# 05_POWER_old.net
KiCad netlist of a schematic drawn in Altium Designer
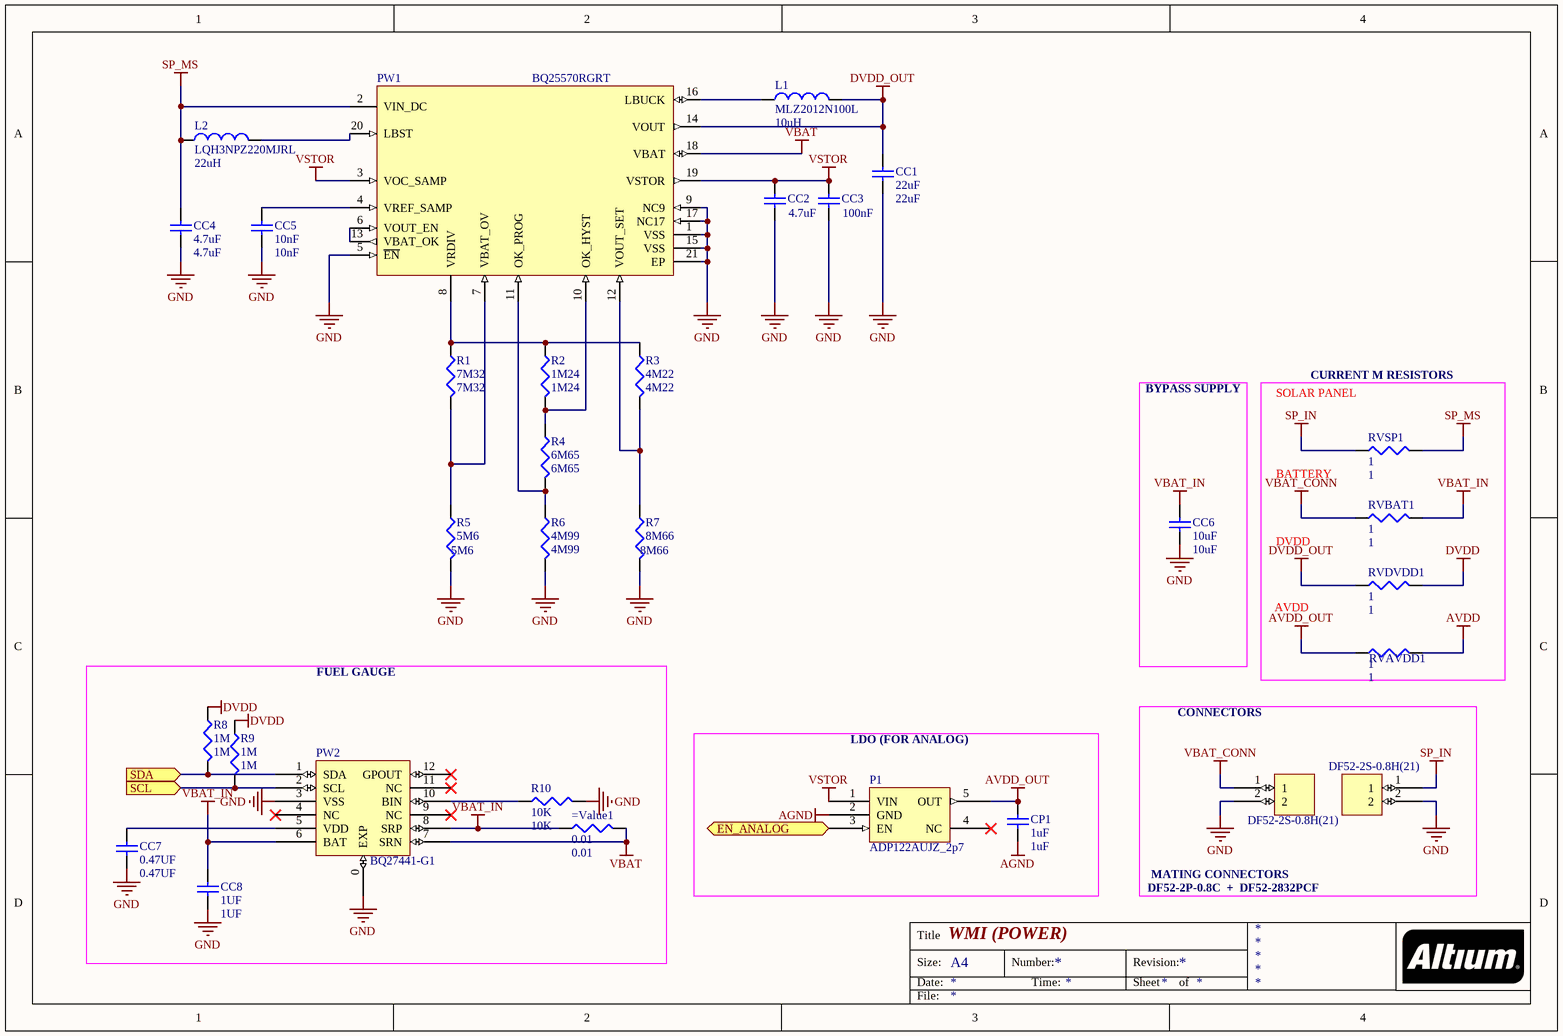
[diagram p0: 05_POWER_old.SchDoc]

(export (version "E")
  (design (tool "Eeschema 10.0.6"))
  (components
    (comp (ref "=Value1")
      (value "0.01")
      (footprint "0402")
      (description "Resistor")
      (fields (field (name "ALTIUM_VALUE") "0.01") (field (name "PUBLISHER") "Altium Limited"))
      (libsource (lib "Miscellaneous Devices") (part "Res3"))
    )
    (comp (ref "CC1")
      (value "22uF")
      (footprint "J1-0603")
      (description "Capacitor (Semiconductor SIM Model)")
      (fields (field (name "ALTIUM_VALUE") "22uF") (field (name "PUBLISHER") "Altium Limited"))
      (libsource (lib "Miscellaneous Devices") (part "Cap Semi"))
    )
    (comp (ref "CC2")
      (value "4.7uF")
      (footprint "0402")
      (description "Capacitor (Semiconductor SIM Model)")
      (fields (field (name "PUBLISHER") "Altium Limited"))
      (libsource (lib "Miscellaneous Devices") (part "Cap Semi"))
    )
    (comp (ref "CC3")
      (value "100nF")
      (footprint "0603")
      (description "Capacitor (Semiconductor SIM Model)")
      (fields (field (name "PUBLISHER") "Altium Limited"))
      (libsource (lib "Miscellaneous Devices") (part "Cap Semi"))
    )
    (comp (ref "CC4")
      (value "4.7uF")
      (footprint "0402")
      (description "Capacitor (Semiconductor SIM Model)")
      (fields (field (name "ALTIUM_VALUE") "4.7uF") (field (name "PUBLISHER") "Altium Limited"))
      (libsource (lib "Miscellaneous Devices") (part "Cap Semi"))
    )
    (comp (ref "CC5")
      (value "10nF")
      (footprint "J1-0603")
      (description "Capacitor (Semiconductor SIM Model)")
      (fields (field (name "ALTIUM_VALUE") "10nF") (field (name "PUBLISHER") "Altium Limited"))
      (libsource (lib "Miscellaneous Devices") (part "Cap Semi"))
    )
    (comp (ref "CC6")
      (value "10uF")
      (footprint "0402")
      (description "Capacitor (Semiconductor SIM Model)")
      (fields (field (name "ALTIUM_VALUE") "10uF") (field (name "PUBLISHER") "Altium Limited"))
      (libsource (lib "Miscellaneous Devices") (part "Cap Semi"))
    )
    (comp (ref "CC7")
      (value "0.47UF")
      (footprint "0402")
      (description "Capacitor (Semiconductor SIM Model)")
      (fields (field (name "ALTIUM_VALUE") "0.47UF") (field (name "PUBLISHER") "Altium Limited"))
      (libsource (lib "Miscellaneous Devices") (part "Cap Semi"))
    )
    (comp (ref "CC8")
      (value "1UF")
      (footprint "0402")
      (description "Capacitor (Semiconductor SIM Model)")
      (fields (field (name "ALTIUM_VALUE") "1UF") (field (name "PUBLISHER") "Altium Limited"))
      (libsource (lib "Miscellaneous Devices") (part "Cap Semi"))
    )
    (comp (ref "CONN_BAT1")
      (value "DF52-2S-0.8H(21)")
      (footprint "DF52-2S-0.8H(21)")
      (libsource (lib "Schlib1") (part "DF52-2S-0.8H(21)"))
    )
    (comp (ref "CONN_P_S1")
      (value "DF52-2S-0.8H(21)")
      (footprint "DF52-2S-0.8H(21)")
      (libsource (lib "") (part "DF52-2S-0.8H(21)_1"))
    )
    (comp (ref "CP1")
      (value "1uF")
      (footprint "0402")
      (description "Capacitor (Semiconductor SIM Model)")
      (fields (field (name "ALTIUM_VALUE") "1uF") (field (name "PUBLISHER") "Altium Limited"))
      (libsource (lib "Miscellaneous Devices") (part "Cap Semi"))
    )
    (comp (ref "L1")
      (value "MLZ2012N100L")
      (footprint "6-0805_N")
      (description "Inductor")
      (fields (field (name "ALTIUM_VALUE") "10uH") (field (name "PUBLISHER") "Altium Limited"))
      (libsource (lib "Miscellaneous Devices") (part "Inductor"))
    )
    (comp (ref "L2")
      (value "LQH3NPZ220MJRL")
      (footprint "1212_PCK")
      (description "Inductor")
      (fields (field (name "ALTIUM_VALUE") "22uH") (field (name "PUBLISHER") "Altium Limited"))
      (libsource (lib "Miscellaneous Devices") (part "Inductor"))
    )
    (comp (ref "P1")
      (value "ADP122AUJZ_2p7")
      (footprint "AD Power Mgt Voltage Reference:UJ-5_N")
      (description "Regulator")
      (libsource (lib "Schlib1") (part "ADP122"))
    )
    (comp (ref "PW1")
      (value "BQ25570RGRT")
      (footprint "VQFN20")
      (description "IC ENERGY HARV CTRLR BATT 20VQFN")
      (fields (field (name "MANUFACTURER") "Texas Instruments"))
      (libsource (lib "Schlib1") (part "BQ25570RGRT"))
    )
    (comp (ref "PW2")
      (value "BQ27441-G1")
      (footprint "DRZ12_SMALL")
      (libsource (lib "Schlib1") (part "BQ27441-G1"))
    )
    (comp (ref "R1")
      (value "7M32")
      (footprint "0402")
      (description "Resistor")
      (fields (field (name "ALTIUM_VALUE") "7M32") (field (name "PUBLISHER") "Altium Limited"))
      (libsource (lib "Miscellaneous Devices") (part "Res3"))
    )
    (comp (ref "R2")
      (value "1M24")
      (footprint "0402")
      (description "Resistor")
      (fields (field (name "ALTIUM_VALUE") "1M24") (field (name "PUBLISHER") "Altium Limited"))
      (libsource (lib "Miscellaneous Devices") (part "Res3"))
    )
    (comp (ref "R3")
      (value "4M22")
      (footprint "0402")
      (description "Resistor")
      (fields (field (name "ALTIUM_VALUE") "4M22") (field (name "PUBLISHER") "Altium Limited"))
      (libsource (lib "Miscellaneous Devices") (part "Res3"))
    )
    (comp (ref "R4")
      (value "6M65")
      (footprint "0402")
      (description "Resistor")
      (fields (field (name "ALTIUM_VALUE") "6M65") (field (name "PUBLISHER") "Altium Limited"))
      (libsource (lib "Miscellaneous Devices") (part "Res3"))
    )
    (comp (ref "R5")
      (value "5M6")
      (footprint "0402")
      (description "Resistor")
      (fields (field (name "ALTIUM_VALUE") "5M6") (field (name "PUBLISHER") "Altium Limited"))
      (libsource (lib "Miscellaneous Devices") (part "Res3"))
    )
    (comp (ref "R6")
      (value "4M99")
      (footprint "0402")
      (description "Resistor")
      (fields (field (name "ALTIUM_VALUE") "4M99") (field (name "PUBLISHER") "Altium Limited"))
      (libsource (lib "Miscellaneous Devices") (part "Res3"))
    )
    (comp (ref "R7")
      (value "8M66")
      (footprint "0402")
      (description "Resistor")
      (fields (field (name "ALTIUM_VALUE") "8M66") (field (name "PUBLISHER") "Altium Limited"))
      (libsource (lib "Miscellaneous Devices") (part "Res3"))
    )
    (comp (ref "R8")
      (value "1M")
      (footprint "0402")
      (description "Resistor")
      (fields (field (name "ALTIUM_VALUE") "1M") (field (name "PUBLISHER") "Altium Limited"))
      (libsource (lib "Miscellaneous Devices") (part "Res3"))
    )
    (comp (ref "R9")
      (value "1M")
      (footprint "0402")
      (description "Resistor")
      (fields (field (name "ALTIUM_VALUE") "1M") (field (name "PUBLISHER") "Altium Limited"))
      (libsource (lib "Miscellaneous Devices") (part "Res3"))
    )
    (comp (ref "R10")
      (value "10K")
      (footprint "0402")
      (description "Resistor")
      (fields (field (name "ALTIUM_VALUE") "10K") (field (name "PUBLISHER") "Altium Limited"))
      (libsource (lib "Miscellaneous Devices") (part "Res3"))
    )
    (comp (ref "RVAVDD1")
      (value "1")
      (footprint "J1-0603")
      (description "Resistor")
      (fields (field (name "ALTIUM_VALUE") "1") (field (name "PUBLISHER") "Altium Limited"))
      (libsource (lib "Miscellaneous Devices") (part "Res3"))
    )
    (comp (ref "RVBAT1")
      (value "1")
      (footprint "J1-0603")
      (description "Resistor")
      (fields (field (name "ALTIUM_VALUE") "1") (field (name "PUBLISHER") "Altium Limited"))
      (libsource (lib "Miscellaneous Devices") (part "Res3"))
    )
    (comp (ref "RVDVDD1")
      (value "1")
      (footprint "J1-0603")
      (description "Resistor")
      (fields (field (name "ALTIUM_VALUE") "1") (field (name "PUBLISHER") "Altium Limited"))
      (libsource (lib "Miscellaneous Devices") (part "Res3"))
    )
    (comp (ref "RVSP1")
      (value "1")
      (footprint "J1-0603")
      (description "Resistor")
      (fields (field (name "ALTIUM_VALUE") "1") (field (name "PUBLISHER") "Altium Limited"))
      (libsource (lib "Miscellaneous Devices") (part "Res3"))
    )
  )
  (nets
    (net (code "1") (name "/EN_ANALOG") (class "Default")
      (node (ref "P1") (pin "3") (pinfunction "EN_3") (pintype "input"))
    )
    (net (code "2") (name "/SCL") (class "Default")
      (node (ref "PW2") (pin "2") (pinfunction "SCL_2") (pintype "bidirectional"))
      (node (ref "R9") (pin "2") (pinfunction "2_2") (pintype "passive"))
    )
    (net (code "3") (name "/SDA") (class "Default")
      (node (ref "PW2") (pin "1") (pinfunction "SDA_1") (pintype "bidirectional"))
      (node (ref "R8") (pin "2") (pinfunction "2_2") (pintype "passive"))
    )
    (net (code "4") (name "AGND") (class "Default")
      (node (ref "CP1") (pin "1") (pinfunction "1_1") (pintype "passive"))
      (node (ref "P1") (pin "2") (pinfunction "GND_2") (pintype "power_in"))
    )
    (net (code "5") (name "AVDD") (class "Default")
      (node (ref "RVAVDD1") (pin "2") (pinfunction "2_2") (pintype "passive"))
    )
    (net (code "6") (name "AVDD_OUT") (class "Default")
      (node (ref "CP1") (pin "2") (pinfunction "2_2") (pintype "passive"))
      (node (ref "P1") (pin "5") (pinfunction "OUT_5") (pintype "output"))
      (node (ref "RVAVDD1") (pin "1") (pinfunction "1_1") (pintype "passive"))
    )
    (net (code "7") (name "DVDD") (class "Default")
      (node (ref "R8") (pin "1") (pinfunction "1_1") (pintype "passive"))
      (node (ref "R9") (pin "1") (pinfunction "1_1") (pintype "passive"))
      (node (ref "RVDVDD1") (pin "2") (pinfunction "2_2") (pintype "passive"))
    )
    (net (code "8") (name "DVDD_OUT") (class "Default")
      (node (ref "CC1") (pin "2") (pinfunction "2_2") (pintype "passive"))
      (node (ref "L1") (pin "2") (pinfunction "2_2") (pintype "passive"))
      (node (ref "PW1") (pin "14") (pinfunction "VOUT_14") (pintype "output"))
      (node (ref "RVDVDD1") (pin "1") (pinfunction "1_1") (pintype "passive"))
    )
    (net (code "9") (name "GND") (class "Default")
      (node (ref "CC1") (pin "1") (pinfunction "1_1") (pintype "passive"))
      (node (ref "CC2") (pin "1") (pinfunction "1_1") (pintype "passive"))
      (node (ref "CC3") (pin "1") (pinfunction "1_1") (pintype "passive"))
      (node (ref "CC4") (pin "1") (pinfunction "1_1") (pintype "passive"))
      (node (ref "CC5") (pin "1") (pinfunction "1_1") (pintype "passive"))
      (node (ref "CC6") (pin "1") (pinfunction "1_1") (pintype "passive"))
      (node (ref "CC7") (pin "1") (pinfunction "1_1") (pintype "passive"))
      (node (ref "CC8") (pin "1") (pinfunction "1_1") (pintype "passive"))
      (node (ref "CONN_BAT1") (pin "2") (pinfunction "2_2") (pintype "bidirectional"))
      (node (ref "CONN_P_S1") (pin "2") (pinfunction "2_2") (pintype "bidirectional"))
      (node (ref "PW1") (pin "1") (pinfunction "VSS_1") (pintype "power_in"))
      (node (ref "PW1") (pin "15") (pinfunction "VSS_15") (pintype "power_in"))
      (node (ref "PW1") (pin "17") (pinfunction "NC17_17") (pintype "input"))
      (node (ref "PW1") (pin "21") (pinfunction "EP_21") (pintype "passive"))
      (node (ref "PW1") (pin "5") (pinfunction "~{EN}_5") (pintype "input"))
      (node (ref "PW1") (pin "9") (pinfunction "NC9_9") (pintype "input"))
      (node (ref "PW2") (pin "0") (pinfunction "EXP_0") (pintype "bidirectional"))
      (node (ref "PW2") (pin "3") (pinfunction "VSS_3") (pintype "power_in"))
      (node (ref "R10") (pin "2") (pinfunction "2_2") (pintype "passive"))
      (node (ref "R5") (pin "2") (pinfunction "2_2") (pintype "passive"))
      (node (ref "R6") (pin "2") (pinfunction "2_2") (pintype "passive"))
      (node (ref "R7") (pin "2") (pinfunction "2_2") (pintype "passive"))
    )
    (net (code "10") (name "Net-(PW1-LBST)") (class "Default")
      (node (ref "L2") (pin "2") (pinfunction "2_2") (pintype "passive"))
      (node (ref "PW1") (pin "20") (pinfunction "LBST_20") (pintype "input"))
    )
    (net (code "11") (name "Net-(PW1-LBUCK)") (class "Default")
      (node (ref "L1") (pin "1") (pinfunction "1_1") (pintype "passive"))
      (node (ref "PW1") (pin "16") (pinfunction "LBUCK_16") (pintype "bidirectional"))
    )
    (net (code "12") (name "Net-(PW1-OK_HYST)") (class "Default")
      (node (ref "PW1") (pin "10") (pinfunction "OK_HYST_10") (pintype "input"))
      (node (ref "R2") (pin "2") (pinfunction "2_2") (pintype "passive"))
      (node (ref "R4") (pin "1") (pinfunction "1_1") (pintype "passive"))
    )
    (net (code "13") (name "Net-(PW1-OK_PROG)") (class "Default")
      (node (ref "PW1") (pin "11") (pinfunction "OK_PROG_11") (pintype "input"))
      (node (ref "R4") (pin "2") (pinfunction "2_2") (pintype "passive"))
      (node (ref "R6") (pin "1") (pinfunction "1_1") (pintype "passive"))
    )
    (net (code "14") (name "Net-(PW1-VBAT_OK)") (class "Default")
      (node (ref "PW1") (pin "13") (pinfunction "VBAT_OK_13") (pintype "output"))
      (node (ref "PW1") (pin "6") (pinfunction "VOUT_EN_6") (pintype "input"))
    )
    (net (code "15") (name "Net-(PW1-VBAT_OV)") (class "Default")
      (node (ref "PW1") (pin "7") (pinfunction "VBAT_OV_7") (pintype "input"))
      (node (ref "R1") (pin "2") (pinfunction "2_2") (pintype "passive"))
      (node (ref "R5") (pin "1") (pinfunction "1_1") (pintype "passive"))
    )
    (net (code "16") (name "Net-(PW1-VOUT_SET)") (class "Default")
      (node (ref "PW1") (pin "12") (pinfunction "VOUT_SET_12") (pintype "input"))
      (node (ref "R3") (pin "2") (pinfunction "2_2") (pintype "passive"))
      (node (ref "R7") (pin "1") (pinfunction "1_1") (pintype "passive"))
    )
    (net (code "17") (name "Net-(PW1-VRDIV)") (class "Default")
      (node (ref "PW1") (pin "8") (pinfunction "VRDIV_8") (pintype "power_in"))
      (node (ref "R1") (pin "1") (pinfunction "1_1") (pintype "passive"))
      (node (ref "R2") (pin "1") (pinfunction "1_1") (pintype "passive"))
      (node (ref "R3") (pin "1") (pinfunction "1_1") (pintype "passive"))
    )
    (net (code "18") (name "Net-(PW1-VREF_SAMP)") (class "Default")
      (node (ref "CC5") (pin "2") (pinfunction "2_2") (pintype "passive"))
      (node (ref "PW1") (pin "4") (pinfunction "VREF_SAMP_4") (pintype "input"))
    )
    (net (code "19") (name "Net-(PW2-BIN)") (class "Default")
      (node (ref "PW2") (pin "10") (pinfunction "BIN_10") (pintype "bidirectional"))
      (node (ref "R10") (pin "1") (pinfunction "1_1") (pintype "passive"))
    )
    (net (code "20") (name "Net-(PW2-VDD)") (class "Default")
      (node (ref "CC7") (pin "2") (pinfunction "2_2") (pintype "passive"))
      (node (ref "PW2") (pin "5") (pinfunction "VDD_5") (pintype "power_in"))
    )
    (net (code "21") (name "SP_IN") (class "Default")
      (node (ref "CONN_P_S1") (pin "1") (pinfunction "1_1") (pintype "bidirectional"))
      (node (ref "RVSP1") (pin "1") (pinfunction "1_1") (pintype "passive"))
    )
    (net (code "22") (name "SP_MS") (class "Default")
      (node (ref "CC4") (pin "2") (pinfunction "2_2") (pintype "passive"))
      (node (ref "L2") (pin "1") (pinfunction "1_1") (pintype "passive"))
      (node (ref "PW1") (pin "2") (pinfunction "VIN_DC_2") (pintype "power_in"))
      (node (ref "RVSP1") (pin "2") (pinfunction "2_2") (pintype "passive"))
    )
    (net (code "23") (name "VBAT") (class "Default")
      (node (ref "=Value1") (pin "2") (pinfunction "2_2") (pintype "passive"))
      (node (ref "PW1") (pin "18") (pinfunction "VBAT_18") (pintype "bidirectional"))
      (node (ref "PW2") (pin "7") (pinfunction "SRN_7") (pintype "bidirectional"))
    )
    (net (code "24") (name "VBAT_CONN") (class "Default")
      (node (ref "CONN_BAT1") (pin "1") (pinfunction "1_1") (pintype "bidirectional"))
      (node (ref "RVBAT1") (pin "1") (pinfunction "1_1") (pintype "passive"))
    )
    (net (code "25") (name "VBAT_IN") (class "Default")
      (node (ref "=Value1") (pin "1") (pinfunction "1_1") (pintype "passive"))
      (node (ref "CC6") (pin "2") (pinfunction "2_2") (pintype "passive"))
      (node (ref "CC8") (pin "2") (pinfunction "2_2") (pintype "passive"))
      (node (ref "PW2") (pin "6") (pinfunction "BAT_6") (pintype "power_in"))
      (node (ref "PW2") (pin "8") (pinfunction "SRP_8") (pintype "bidirectional"))
      (node (ref "RVBAT1") (pin "2") (pinfunction "2_2") (pintype "passive"))
    )
    (net (code "26") (name "VSTOR") (class "Default")
      (node (ref "CC2") (pin "2") (pinfunction "2_2") (pintype "passive"))
      (node (ref "CC3") (pin "2") (pinfunction "2_2") (pintype "passive"))
      (node (ref "P1") (pin "1") (pinfunction "VIN_1") (pintype "power_in"))
      (node (ref "PW1") (pin "19") (pinfunction "VSTOR_19") (pintype "output"))
      (node (ref "PW1") (pin "3") (pinfunction "VOC_SAMP_3") (pintype "input"))
    )
    (net (code "27") (name "unconnected-(P1-NC-Pad4)") (class "Default")
      (node (ref "P1") (pin "4") (pinfunction "NC_4") (pintype "passive+no_connect"))
    )
    (net (code "28") (name "unconnected-(PW2-GPOUT-Pad12)") (class "Default")
      (node (ref "PW2") (pin "12") (pinfunction "GPOUT_12") (pintype "bidirectional+no_connect"))
    )
    (net (code "29") (name "unconnected-(PW2-NC-Pad4)") (class "Default")
      (node (ref "PW2") (pin "4") (pinfunction "NC_4") (pintype "passive+no_connect"))
    )
    (net (code "30") (name "unconnected-(PW2-NC-Pad9)") (class "Default")
      (node (ref "PW2") (pin "9") (pinfunction "NC_9") (pintype "passive+no_connect"))
    )
    (net (code "31") (name "unconnected-(PW2-NC-Pad11)") (class "Default")
      (node (ref "PW2") (pin "11") (pinfunction "NC_11") (pintype "passive+no_connect"))
    )
  )
)
